# avruler.net
KiCad netlist of a schematic drawn in EAGLE
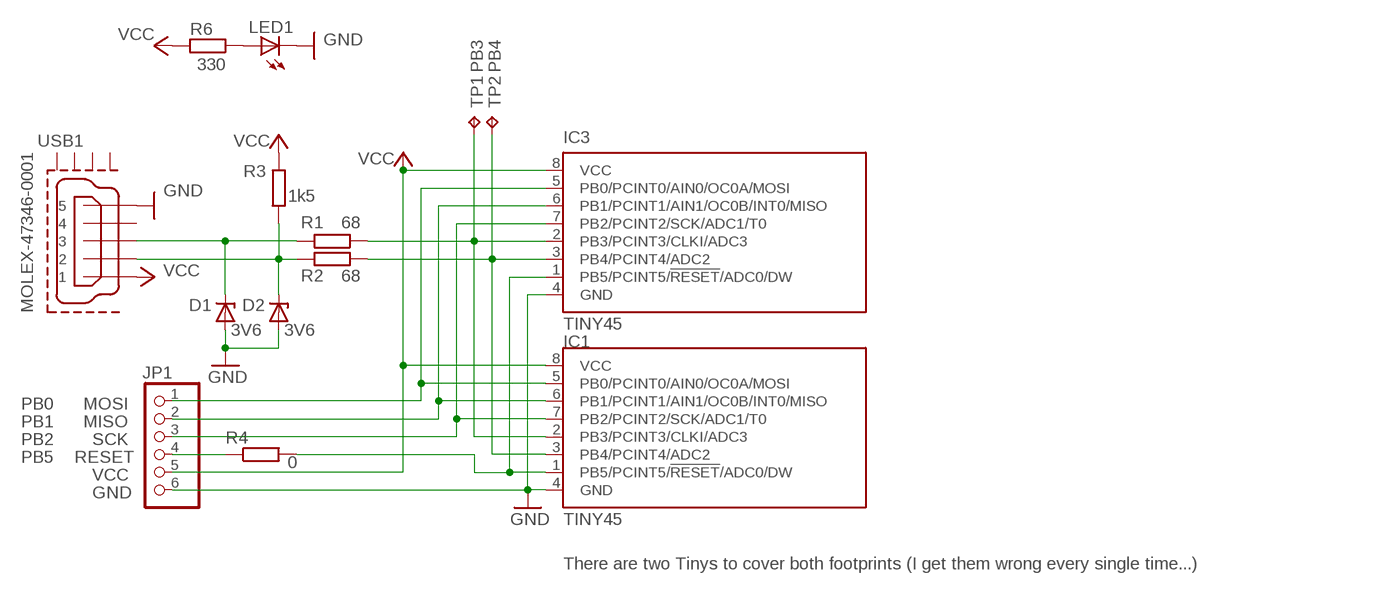
[diagram p0: schematic, sheet 1]

(export (version "E")
  (design (tool "Eeschema 10.0.6"))
  (components
    (comp (ref "D1")
      (value "3V6")
      (footprint "eagle-import:SOD80C")
      (libsource (lib "eagle-import") (part "ZENER-DIODESOD80C"))
    )
    (comp (ref "D2")
      (value "3V6")
      (footprint "eagle-import:SOD80C")
      (libsource (lib "eagle-import") (part "ZENER-DIODESOD80C"))
    )
    (comp (ref "IC1")
      (value "TINY45")
      (footprint "eagle-import:8S1")
      (fields (field (name "MPN") "ATTINY13-20SSU"))
      (libsource (lib "eagle-import") (part "TINY13SSU-20"))
    )
    (comp (ref "IC3")
      (value "TINY45")
      (footprint "eagle-import:8S2")
      (fields (field (name "MPN") "ATTINY13-20SU"))
      (libsource (lib "eagle-import") (part "TINY13SU-20"))
    )
    (comp (ref "JP1")
      (value "PINHD-1X6/90")
      (footprint "eagle-import:1X06_90")
      (libsource (lib "eagle-import") (part "PINHD-1X6/90"))
    )
    (comp (ref "LED1")
      (value "LEDCHIPLED_1206")
      (footprint "eagle-import:CHIPLED_1206")
      (libsource (lib "eagle-import") (part "LEDCHIPLED_1206"))
    )
    (comp (ref "R1")
      (value "68")
      (footprint "eagle-import:M1206")
      (libsource (lib "eagle-import") (part "R-EU_M1206"))
    )
    (comp (ref "R2")
      (value "68")
      (footprint "eagle-import:M1206")
      (libsource (lib "eagle-import") (part "R-EU_M1206"))
    )
    (comp (ref "R3")
      (value "1k5")
      (footprint "eagle-import:M1206")
      (libsource (lib "eagle-import") (part "R-EU_M1206"))
    )
    (comp (ref "R4")
      (value "0")
      (footprint "eagle-import:M1206")
      (libsource (lib "eagle-import") (part "R-EU_M1206"))
    )
    (comp (ref "R6")
      (value "330")
      (footprint "eagle-import:M1206")
      (libsource (lib "eagle-import") (part "R-EU_M1206"))
    )
    (comp (ref "TP1")
      (value "TPTP14SQ")
      (footprint "eagle-import:TP14SQ")
      (libsource (lib "eagle-import") (part "TPTP14SQ"))
    )
    (comp (ref "TP2")
      (value "TPTP14SQ")
      (footprint "eagle-import:TP14SQ")
      (libsource (lib "eagle-import") (part "TPTP14SQ"))
    )
    (comp (ref "USB1")
      (value "MOLEX-47346-0001")
      (footprint "eagle-import:MOLEX-47364-0001")
      (libsource (lib "eagle-import") (part "MOLEX-47346-0001"))
    )
  )
  (nets
    (net (code "1") (name "GND") (class "Default")
      (node (ref "D1") (pin "A") (pinfunction "A_A") (pintype "passive"))
      (node (ref "D2") (pin "A") (pinfunction "A_A") (pintype "passive"))
      (node (ref "IC1") (pin "4") (pinfunction "GND_4") (pintype "power_in"))
      (node (ref "IC3") (pin "4") (pinfunction "GND_4") (pintype "power_in"))
      (node (ref "JP1") (pin "6") (pinfunction "6_6") (pintype "passive"))
      (node (ref "LED1") (pin "C") (pinfunction "C_C") (pintype "passive"))
      (node (ref "USB1") (pin "5") (pinfunction "5_5") (pintype "input"))
    )
    (net (code "2") (name "Net-(D1-PadC)") (class "Default")
      (node (ref "D1") (pin "C") (pinfunction "C_C") (pintype "passive"))
      (node (ref "R1") (pin "2") (pinfunction "2_2") (pintype "passive"))
      (node (ref "USB1") (pin "3") (pinfunction "3_3") (pintype "input"))
    )
    (net (code "3") (name "Net-(D2-PadC)") (class "Default")
      (node (ref "D2") (pin "C") (pinfunction "C_C") (pintype "passive"))
      (node (ref "R2") (pin "2") (pinfunction "2_2") (pintype "passive"))
      (node (ref "R3") (pin "2") (pinfunction "2_2") (pintype "passive"))
      (node (ref "USB1") (pin "2") (pinfunction "2_2") (pintype "input"))
    )
    (net (code "4") (name "Net-(IC1-PB0{slash}PCINT0{slash}AIN0{slash}OC0A{slash}MOSI)") (class "Default")
      (node (ref "IC1") (pin "5") (pinfunction "PB0/PCINT0/AIN0/OC0A/MOSI_5") (pintype "bidirectional"))
      (node (ref "IC3") (pin "5") (pinfunction "PB0/PCINT0/AIN0/OC0A/MOSI_5") (pintype "bidirectional"))
      (node (ref "JP1") (pin "1") (pinfunction "1_1") (pintype "passive"))
    )
    (net (code "5") (name "Net-(IC1-PB1{slash}PCINT1{slash}AIN1{slash}OC0B{slash}INT0{slash}MISO)") (class "Default")
      (node (ref "IC1") (pin "6") (pinfunction "PB1/PCINT1/AIN1/OC0B/INT0/MISO_6") (pintype "bidirectional"))
      (node (ref "IC3") (pin "6") (pinfunction "PB1/PCINT1/AIN1/OC0B/INT0/MISO_6") (pintype "bidirectional"))
      (node (ref "JP1") (pin "2") (pinfunction "2_2") (pintype "passive"))
    )
    (net (code "6") (name "Net-(IC1-PB2{slash}PCINT2{slash}SCK{slash}ADC1{slash}T0)") (class "Default")
      (node (ref "IC1") (pin "7") (pinfunction "PB2/PCINT2/SCK/ADC1/T0_7") (pintype "bidirectional"))
      (node (ref "IC3") (pin "7") (pinfunction "PB2/PCINT2/SCK/ADC1/T0_7") (pintype "bidirectional"))
      (node (ref "JP1") (pin "3") (pinfunction "3_3") (pintype "passive"))
    )
    (net (code "7") (name "Net-(IC1-PB3{slash}PCINT3{slash}CLKI{slash}ADC3)") (class "Default")
      (node (ref "IC1") (pin "2") (pinfunction "PB3/PCINT3/CLKI/ADC3_2") (pintype "bidirectional"))
      (node (ref "IC3") (pin "2") (pinfunction "PB3/PCINT3/CLKI/ADC3_2") (pintype "bidirectional"))
      (node (ref "R1") (pin "1") (pinfunction "1_1") (pintype "passive"))
      (node (ref "TP1") (pin "TP") (pinfunction "TP_TP") (pintype "input"))
    )
    (net (code "8") (name "Net-(IC1-PB4{slash}PCINT4{slash}ADC2)") (class "Default")
      (node (ref "IC1") (pin "3") (pinfunction "PB4/PCINT4/ADC2_3") (pintype "bidirectional"))
      (node (ref "IC3") (pin "3") (pinfunction "PB4/PCINT4/ADC2_3") (pintype "bidirectional"))
      (node (ref "R2") (pin "1") (pinfunction "1_1") (pintype "passive"))
      (node (ref "TP2") (pin "TP") (pinfunction "TP_TP") (pintype "input"))
    )
    (net (code "9") (name "Net-(IC1-PB5{slash}PCINT5{slash}~{RESET}{slash}ADC0{slash}DW)") (class "Default")
      (node (ref "IC1") (pin "1") (pinfunction "PB5/PCINT5/~{RESET}/ADC0/DW_1") (pintype "bidirectional"))
      (node (ref "IC3") (pin "1") (pinfunction "PB5/PCINT5/~{RESET}/ADC0/DW_1") (pintype "bidirectional"))
      (node (ref "R4") (pin "2") (pinfunction "2_2") (pintype "passive"))
    )
    (net (code "10") (name "Net-(JP1-Pad4)") (class "Default")
      (node (ref "JP1") (pin "4") (pinfunction "4_4") (pintype "passive"))
      (node (ref "R4") (pin "1") (pinfunction "1_1") (pintype "passive"))
    )
    (net (code "11") (name "Net-(LED1-PadA)") (class "Default")
      (node (ref "LED1") (pin "A") (pinfunction "A_A") (pintype "passive"))
      (node (ref "R6") (pin "1") (pinfunction "1_1") (pintype "passive"))
    )
    (net (code "12") (name "VCC") (class "Default")
      (node (ref "IC1") (pin "8") (pinfunction "VCC_8") (pintype "power_in"))
      (node (ref "IC3") (pin "8") (pinfunction "VCC_8") (pintype "power_in"))
      (node (ref "JP1") (pin "5") (pinfunction "5_5") (pintype "passive"))
      (node (ref "R3") (pin "1") (pinfunction "1_1") (pintype "passive"))
      (node (ref "R6") (pin "2") (pinfunction "2_2") (pintype "passive"))
      (node (ref "USB1") (pin "1") (pinfunction "1_1") (pintype "input"))
    )
    (net (code "13") (name "unconnected-(USB1-Pad4)") (class "Default")
      (node (ref "USB1") (pin "4") (pinfunction "4_4") (pintype "input"))
    )
    (net (code "14") (name "unconnected-(USB1-PadGND1)") (class "Default")
      (node (ref "USB1") (pin "GND1") (pinfunction "GND1_GND1") (pintype "bidirectional"))
    )
    (net (code "15") (name "unconnected-(USB1-PadGND2)") (class "Default")
      (node (ref "USB1") (pin "GND2") (pinfunction "GND2_GND2") (pintype "bidirectional"))
    )
    (net (code "16") (name "unconnected-(USB1-PadGND3)") (class "Default")
      (node (ref "USB1") (pin "GND3") (pinfunction "GND3_GND3") (pintype "bidirectional"))
    )
    (net (code "17") (name "unconnected-(USB1-PadGND4)") (class "Default")
      (node (ref "USB1") (pin "GND4") (pinfunction "GND4_GND4") (pintype "bidirectional"))
    )
  )
)
